# WIBL.net
KiCad netlist of a schematic drawn in EAGLE
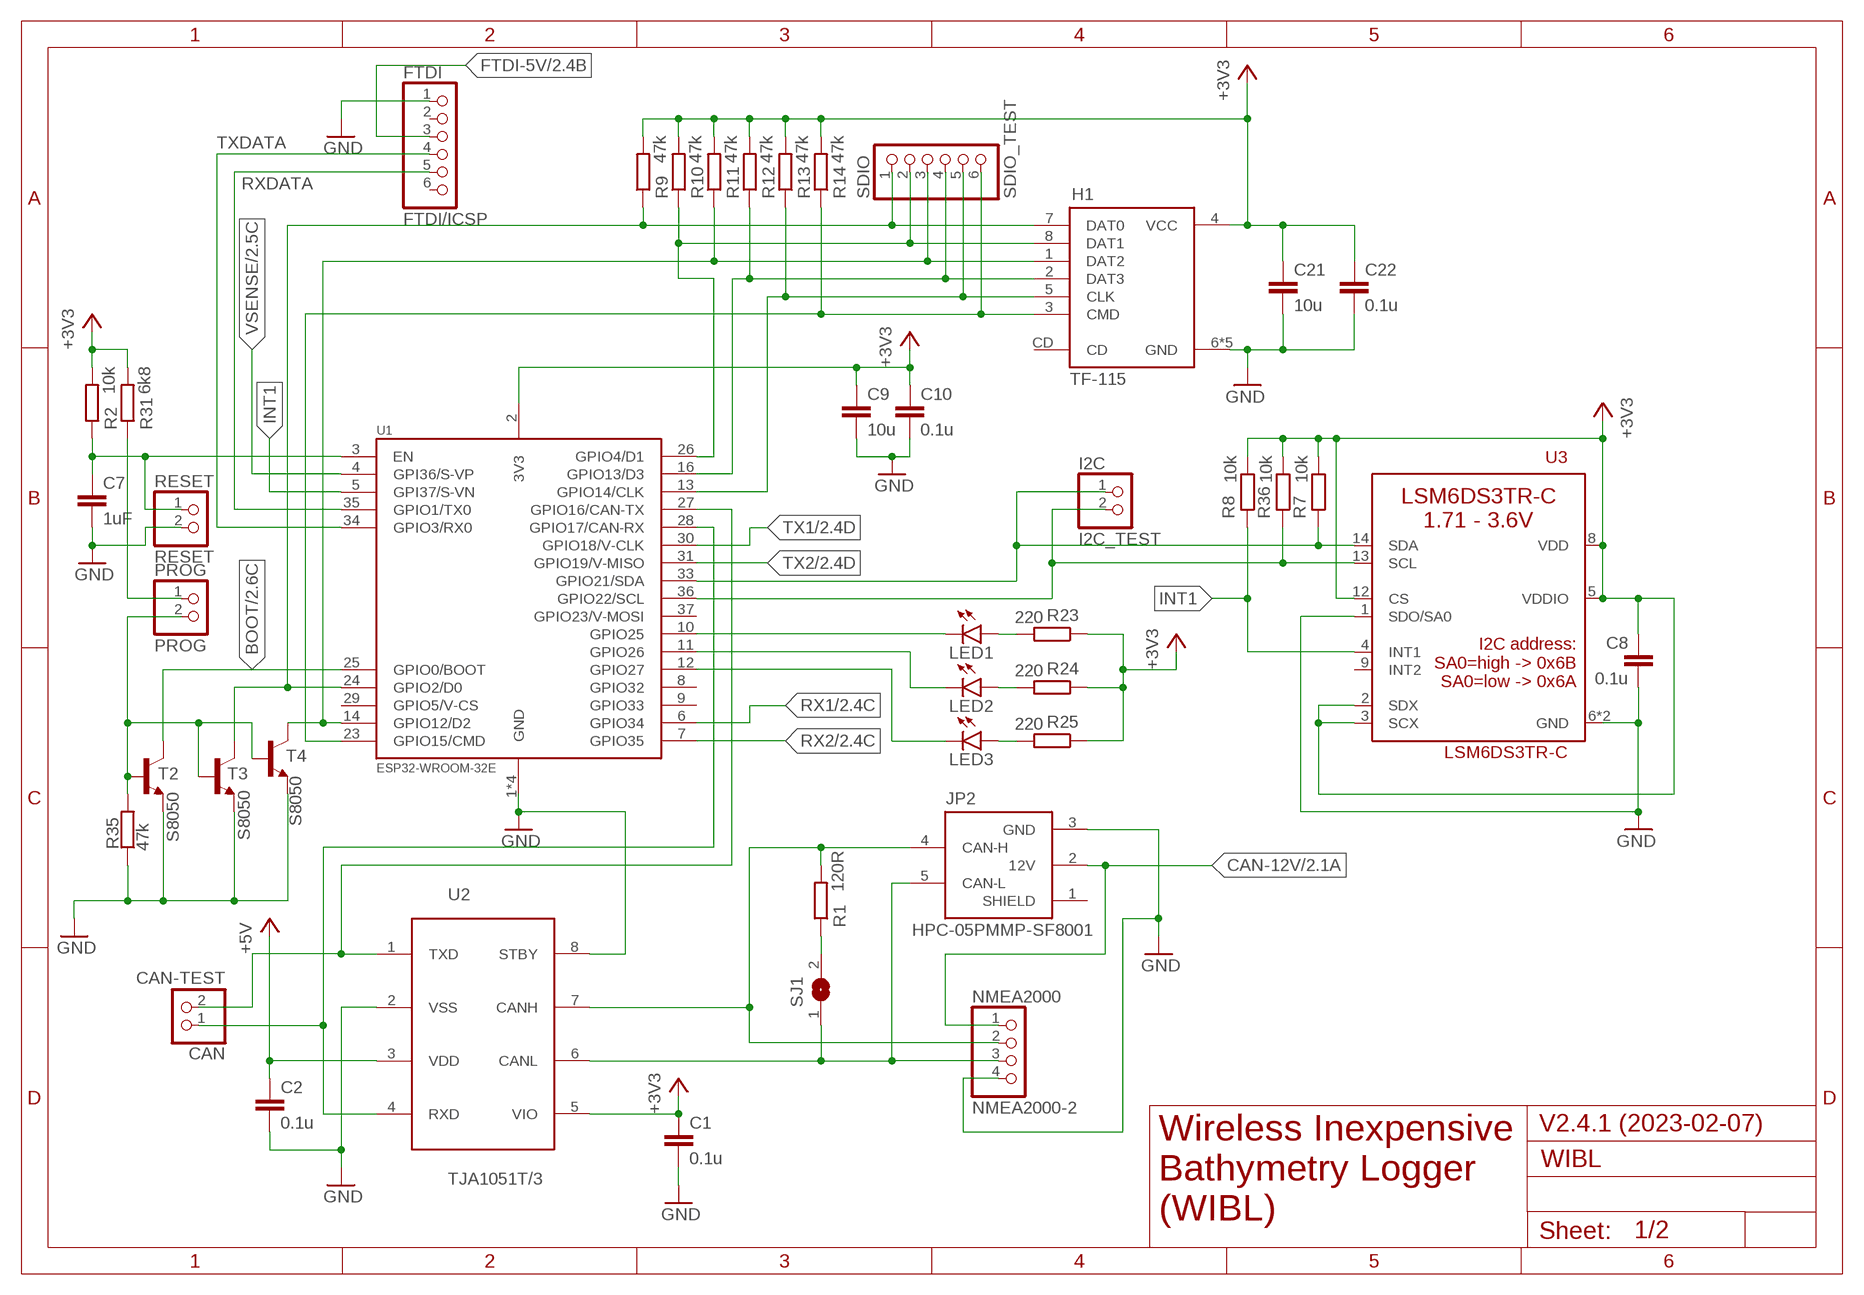
[diagram p0: schematic, sheet 1]
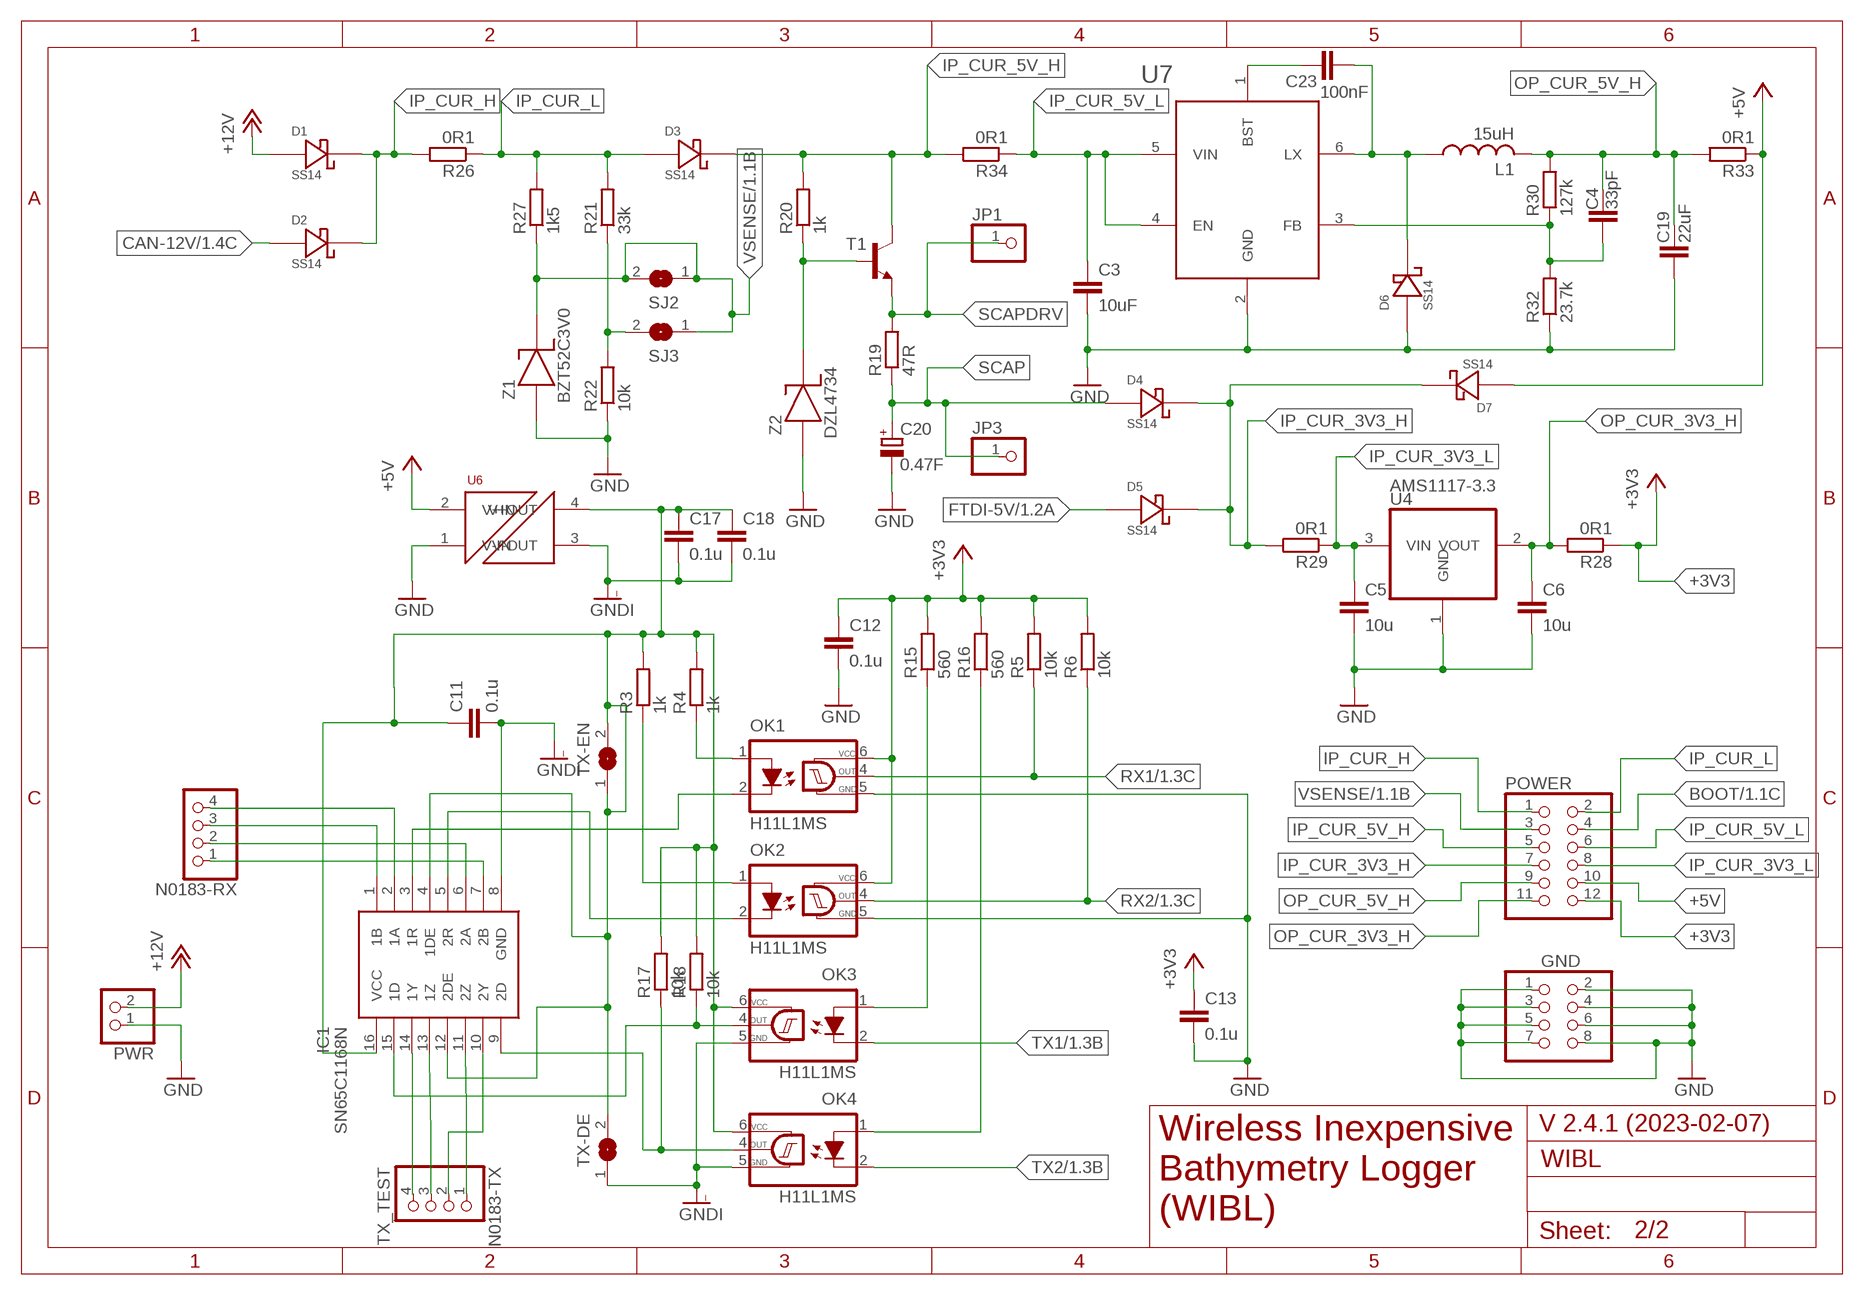
[diagram p1: schematic, sheet 2]

(export (version "E")
  (design (tool "Eeschema 10.0.6"))
  (components
    (comp (ref "C3")
      (value "10uF")
      (footprint "eagle-import:C1206")
      (libsource (lib "eagle-import") (part "C-EUC1206"))
    )
    (comp (ref "C4")
      (value "33pF")
      (footprint "eagle-import:C0603")
      (libsource (lib "eagle-import") (part "C-EUC0603"))
    )
    (comp (ref "C5")
      (value "10u")
      (footprint "eagle-import:C0805")
      (libsource (lib "eagle-import") (part "C-EUC0805"))
    )
    (comp (ref "C6")
      (value "10u")
      (footprint "eagle-import:C0805")
      (libsource (lib "eagle-import") (part "C-EUC0805"))
    )
    (comp (ref "C11")
      (value "0.1u")
      (footprint "eagle-import:C0805")
      (libsource (lib "eagle-import") (part "C-EUC0805"))
    )
    (comp (ref "C12")
      (value "0.1u")
      (footprint "eagle-import:C0805")
      (libsource (lib "eagle-import") (part "C-EUC0805"))
    )
    (comp (ref "C13")
      (value "0.1u")
      (footprint "eagle-import:C0805")
      (libsource (lib "eagle-import") (part "C-EUC0805"))
    )
    (comp (ref "C17")
      (value "0.1u")
      (footprint "eagle-import:C0805")
      (libsource (lib "eagle-import") (part "C-EUC0805"))
    )
    (comp (ref "C18")
      (value "0.1u")
      (footprint "eagle-import:C0805")
      (libsource (lib "eagle-import") (part "C-EUC0805"))
    )
    (comp (ref "C19")
      (value "22uF")
      (footprint "eagle-import:C0603")
      (libsource (lib "eagle-import") (part "C-EUC0603"))
    )
    (comp (ref "C20")
      (value "0.47F")
      (footprint "eagle-import:P128-50")
      (libsource (lib "eagle-import") (part "CPOL-EUP128-50"))
    )
    (comp (ref "C23")
      (value "100nF")
      (footprint "eagle-import:C0402")
      (libsource (lib "eagle-import") (part "C0402"))
    )
    (comp (ref "D1")
      (value "SS14")
      (footprint "eagle-import:DO-214AC")
      (libsource (lib "eagle-import") (part "SS14"))
    )
    (comp (ref "D2")
      (value "SS14")
      (footprint "eagle-import:DO-214AC")
      (libsource (lib "eagle-import") (part "SS14"))
    )
    (comp (ref "D3")
      (value "SS14")
      (footprint "eagle-import:DO-214AC")
      (libsource (lib "eagle-import") (part "SS14"))
    )
    (comp (ref "D4")
      (value "SS14")
      (footprint "eagle-import:DO-214AC")
      (libsource (lib "eagle-import") (part "SS14"))
    )
    (comp (ref "D5")
      (value "SS14")
      (footprint "eagle-import:DO-214AC")
      (libsource (lib "eagle-import") (part "SS14"))
    )
    (comp (ref "D6")
      (value "SS14")
      (footprint "eagle-import:DO-214AC")
      (libsource (lib "eagle-import") (part "SS14"))
    )
    (comp (ref "D7")
      (value "SS14")
      (footprint "eagle-import:DO-214AC")
      (libsource (lib "eagle-import") (part "SS14"))
    )
    (comp (ref "GND")
      (value "PINHD-2X4")
      (footprint "eagle-import:2X04")
      (libsource (lib "eagle-import") (part "PINHD-2X4"))
    )
    (comp (ref "IC1")
      (value "SN65C1168N")
      (footprint "eagle-import:DIP794W53P254L1930H508Q16N")
      (fields (field (name "MOUSER_PART_NUMBER") "595-SN65C1168N"))
      (libsource (lib "eagle-import") (part "SN65C1168N"))
    )
    (comp (ref "JP1")
      (value "PINHD-1X1")
      (footprint "eagle-import:1X01")
      (libsource (lib "eagle-import") (part "PINHD-1X1"))
    )
    (comp (ref "JP3")
      (value "PINHD-1X1")
      (footprint "eagle-import:1X01")
      (libsource (lib "eagle-import") (part "PINHD-1X1"))
    )
    (comp (ref "L1")
      (value "15uH")
      (footprint "eagle-import:MWSA0603S")
      (libsource (lib "eagle-import") (part "MWSA0603S"))
    )
    (comp (ref "N0183-RX")
      (value "PINHD-1X4")
      (footprint "eagle-import:1X04")
      (libsource (lib "eagle-import") (part "PINHD-1X4"))
    )
    (comp (ref "N0183-TX")
      (value "TX_TEST")
      (footprint "eagle-import:1X04")
      (libsource (lib "eagle-import") (part "PINHD-1X4"))
    )
    (comp (ref "OK1")
      (value "H11L1MS")
      (footprint "eagle-import:DIL6-SMD")
      (libsource (lib "eagle-import") (part "H11LMS1"))
    )
    (comp (ref "OK2")
      (value "H11L1MS")
      (footprint "eagle-import:DIL6-SMD")
      (libsource (lib "eagle-import") (part "H11LMS1"))
    )
    (comp (ref "OK3")
      (value "H11L1MS")
      (footprint "eagle-import:DIL6-SMD")
      (libsource (lib "eagle-import") (part "H11LMS1"))
    )
    (comp (ref "OK4")
      (value "H11L1MS")
      (footprint "eagle-import:DIL6-SMD")
      (libsource (lib "eagle-import") (part "H11LMS1"))
    )
    (comp (ref "POWER")
      (value "PINHD-2X6")
      (footprint "eagle-import:2X06")
      (libsource (lib "eagle-import") (part "PINHD-2X6"))
    )
    (comp (ref "PWR")
      (value "PINHD-1X2")
      (footprint "eagle-import:1X02")
      (libsource (lib "eagle-import") (part "PINHD-1X2"))
    )
    (comp (ref "R3")
      (value "1k")
      (footprint "eagle-import:R0805")
      (libsource (lib "eagle-import") (part "R-EU_R0805"))
    )
    (comp (ref "R4")
      (value "1k")
      (footprint "eagle-import:R0805")
      (libsource (lib "eagle-import") (part "R-EU_R0805"))
    )
    (comp (ref "R5")
      (value "10k")
      (footprint "eagle-import:R0805")
      (libsource (lib "eagle-import") (part "R-EU_R0805"))
    )
    (comp (ref "R6")
      (value "10k")
      (footprint "eagle-import:R0805")
      (libsource (lib "eagle-import") (part "R-EU_R0805"))
    )
    (comp (ref "R15")
      (value "560")
      (footprint "eagle-import:R0805")
      (libsource (lib "eagle-import") (part "R-EU_R0805"))
    )
    (comp (ref "R16")
      (value "560")
      (footprint "eagle-import:R0805")
      (libsource (lib "eagle-import") (part "R-EU_R0805"))
    )
    (comp (ref "R17")
      (value "10k")
      (footprint "eagle-import:R0805")
      (libsource (lib "eagle-import") (part "R-EU_R0805"))
    )
    (comp (ref "R18")
      (value "10k")
      (footprint "eagle-import:R0805")
      (libsource (lib "eagle-import") (part "R-EU_R0805"))
    )
    (comp (ref "R19")
      (value "47R")
      (footprint "eagle-import:R0805")
      (libsource (lib "eagle-import") (part "R-EU_R0805"))
    )
    (comp (ref "R20")
      (value "1k")
      (footprint "eagle-import:R0805")
      (libsource (lib "eagle-import") (part "R-EU_R0805"))
    )
    (comp (ref "R21")
      (value "33k")
      (footprint "eagle-import:R0805")
      (libsource (lib "eagle-import") (part "R-EU_R0805"))
    )
    (comp (ref "R22")
      (value "10k")
      (footprint "eagle-import:R0805")
      (libsource (lib "eagle-import") (part "R-EU_R0805"))
    )
    (comp (ref "R26")
      (value "0R1")
      (footprint "eagle-import:R0603")
      (libsource (lib "eagle-import") (part "R-EU_R0603"))
    )
    (comp (ref "R27")
      (value "1k5")
      (footprint "eagle-import:R0805")
      (libsource (lib "eagle-import") (part "R-EU_R0805"))
    )
    (comp (ref "R28")
      (value "0R1")
      (footprint "eagle-import:R0603")
      (libsource (lib "eagle-import") (part "R-EU_R0603"))
    )
    (comp (ref "R29")
      (value "0R1")
      (footprint "eagle-import:R0603")
      (libsource (lib "eagle-import") (part "R-EU_R0603"))
    )
    (comp (ref "R30")
      (value "127k")
      (footprint "eagle-import:R0603")
      (libsource (lib "eagle-import") (part "R-EU_R0603"))
    )
    (comp (ref "R32")
      (value "23.7k")
      (footprint "eagle-import:R0603")
      (libsource (lib "eagle-import") (part "R-EU_R0603"))
    )
    (comp (ref "R33")
      (value "0R1")
      (footprint "eagle-import:R0603")
      (libsource (lib "eagle-import") (part "R-EU_R0603"))
    )
    (comp (ref "R34")
      (value "0R1")
      (footprint "eagle-import:R0603")
      (libsource (lib "eagle-import") (part "R-EU_R0603"))
    )
    (comp (ref "SJ2") (value "SJ") (footprint "eagle-import:SJ") (libsource (lib "eagle-import") (part "SJ")))
    (comp (ref "SJ3") (value "SJ") (footprint "eagle-import:SJ") (libsource (lib "eagle-import") (part "SJ")))
    (comp (ref "T1")
      (value "BC817-16-NPN-SOT23-BEC")
      (footprint "eagle-import:SOT23-BEC")
      (libsource (lib "eagle-import") (part "-NPN-SOT23-BECBC817-16"))
    )
    (comp (ref "TX-DE")
      (value "SJ")
      (footprint "eagle-import:SJ")
      (libsource (lib "eagle-import") (part "SJ"))
    )
    (comp (ref "TX-EN")
      (value "SJ")
      (footprint "eagle-import:SJ")
      (libsource (lib "eagle-import") (part "SJ"))
    )
    (comp (ref "U4")
      (value "AMS1117-3.3")
      (footprint "eagle-import:SOT223")
      (fields (field (name "MPN") "REG1117"))
      (libsource (lib "eagle-import") (part "REG1117"))
    )
    (comp (ref "U6")
      (value "RFM-0505S")
      (footprint "eagle-import:RFM-0505S")
      (libsource (lib "eagle-import") (part "RFM-0505S"))
    )
    (comp (ref "U7")
      (value "BL9352A")
      (footprint "eagle-import:SOT-23-6L")
      (libsource (lib "eagle-import") (part "BL9352A"))
    )
    (comp (ref "Z1")
      (value "BZT52C3V0")
      (footprint "eagle-import:SOD123")
      (libsource (lib "eagle-import") (part "BZT52C3V0"))
    )
    (comp (ref "Z2")
      (value "DZL4734")
      (footprint "eagle-import:SOD-123FL")
      (libsource (lib "eagle-import") (part "DZL4734"))
    )
    (comp (ref "C1")
      (value "0.1u")
      (footprint "eagle-import:C0805")
      (libsource (lib "eagle-import") (part "C-EUC0805"))
    )
    (comp (ref "C2")
      (value "0.1u")
      (footprint "eagle-import:C0805")
      (libsource (lib "eagle-import") (part "C-EUC0805"))
    )
    (comp (ref "C7")
      (value "1uF")
      (footprint "eagle-import:C0805")
      (libsource (lib "eagle-import") (part "C-EUC0805"))
    )
    (comp (ref "C8")
      (value "0.1u")
      (footprint "eagle-import:C0805")
      (libsource (lib "eagle-import") (part "C-EUC0805"))
    )
    (comp (ref "C9")
      (value "10u")
      (footprint "eagle-import:C0805")
      (libsource (lib "eagle-import") (part "C-EUC0805"))
    )
    (comp (ref "C10")
      (value "0.1u")
      (footprint "eagle-import:C0805")
      (libsource (lib "eagle-import") (part "C-EUC0805"))
    )
    (comp (ref "C21")
      (value "10u")
      (footprint "eagle-import:C0805")
      (libsource (lib "eagle-import") (part "C-EUC0805"))
    )
    (comp (ref "C22")
      (value "0.1u")
      (footprint "eagle-import:C0805")
      (libsource (lib "eagle-import") (part "C-EUC0805"))
    )
    (comp (ref "CAN")
      (value "CAN-TEST")
      (footprint "eagle-import:1X02")
      (libsource (lib "eagle-import") (part "PINHD-1X2"))
    )
    (comp (ref "FTDI")
      (value "FTDI/ICSP")
      (footprint "eagle-import:1X06")
      (libsource (lib "eagle-import") (part "PINHD-1X6"))
    )
    (comp (ref "H1")
      (value "TF-115")
      (footprint "eagle-import:XUNPU-MICROSD-SOCKET")
      (libsource (lib "eagle-import") (part "XUNPU-MICROSD-SOCKET"))
    )
    (comp (ref "I2C")
      (value "I2C_TEST")
      (footprint "eagle-import:1X02")
      (libsource (lib "eagle-import") (part "PINHD-1X2"))
    )
    (comp (ref "JP2")
      (value "HPC-05PMMP-SF8001")
      (footprint "eagle-import:NMEA2000")
      (libsource (lib "eagle-import") (part "NMEA2000"))
    )
    (comp (ref "LED1")
      (value "LEDCHIP-LED0603")
      (footprint "eagle-import:CHIP-LED0603")
      (libsource (lib "eagle-import") (part "LEDCHIP-LED0603"))
    )
    (comp (ref "LED2")
      (value "LEDCHIP-LED0603")
      (footprint "eagle-import:CHIP-LED0603")
      (libsource (lib "eagle-import") (part "LEDCHIP-LED0603"))
    )
    (comp (ref "LED3")
      (value "LEDCHIP-LED0603")
      (footprint "eagle-import:CHIP-LED0603")
      (libsource (lib "eagle-import") (part "LEDCHIP-LED0603"))
    )
    (comp (ref "NMEA2000")
      (value "NMEA2000-2")
      (footprint "eagle-import:1X04")
      (libsource (lib "eagle-import") (part "PINHD-1X4"))
    )
    (comp (ref "PROG")
      (value "PROG")
      (footprint "eagle-import:1X02")
      (libsource (lib "eagle-import") (part "PINHD-1X2"))
    )
    (comp (ref "R1")
      (value "120R")
      (footprint "eagle-import:R0805")
      (libsource (lib "eagle-import") (part "R-EU_R0805"))
    )
    (comp (ref "R2")
      (value "10k")
      (footprint "eagle-import:R0805")
      (libsource (lib "eagle-import") (part "R-EU_R0805"))
    )
    (comp (ref "R7")
      (value "10k")
      (footprint "eagle-import:R0805")
      (libsource (lib "eagle-import") (part "R-EU_R0805"))
    )
    (comp (ref "R8")
      (value "10k")
      (footprint "eagle-import:R0805")
      (libsource (lib "eagle-import") (part "R-EU_R0805"))
    )
    (comp (ref "R9")
      (value "47k")
      (footprint "eagle-import:R0805")
      (libsource (lib "eagle-import") (part "R-EU_R0805"))
    )
    (comp (ref "R10")
      (value "47k")
      (footprint "eagle-import:R0805")
      (libsource (lib "eagle-import") (part "R-EU_R0805"))
    )
    (comp (ref "R11")
      (value "47k")
      (footprint "eagle-import:R0805")
      (libsource (lib "eagle-import") (part "R-EU_R0805"))
    )
    (comp (ref "R12")
      (value "47k")
      (footprint "eagle-import:R0805")
      (libsource (lib "eagle-import") (part "R-EU_R0805"))
    )
    (comp (ref "R13")
      (value "47k")
      (footprint "eagle-import:R0805")
      (libsource (lib "eagle-import") (part "R-EU_R0805"))
    )
    (comp (ref "R14")
      (value "47k")
      (footprint "eagle-import:R0805")
      (libsource (lib "eagle-import") (part "R-EU_R0805"))
    )
    (comp (ref "R23")
      (value "220")
      (footprint "eagle-import:R0805")
      (libsource (lib "eagle-import") (part "R-EU_R0805"))
    )
    (comp (ref "R24")
      (value "220")
      (footprint "eagle-import:R0805")
      (libsource (lib "eagle-import") (part "R-EU_R0805"))
    )
    (comp (ref "R25")
      (value "220")
      (footprint "eagle-import:R0805")
      (libsource (lib "eagle-import") (part "R-EU_R0805"))
    )
    (comp (ref "R31")
      (value "6k8")
      (footprint "eagle-import:R0805")
      (libsource (lib "eagle-import") (part "R-EU_R0805"))
    )
    (comp (ref "R35")
      (value "47k")
      (footprint "eagle-import:R0805")
      (libsource (lib "eagle-import") (part "R-EU_R0805"))
    )
    (comp (ref "R36")
      (value "10k")
      (footprint "eagle-import:R0805")
      (libsource (lib "eagle-import") (part "R-EU_R0805"))
    )
    (comp (ref "RESET")
      (value "RESET")
      (footprint "eagle-import:1X02")
      (libsource (lib "eagle-import") (part "PINHD-1X2"))
    )
    (comp (ref "SDIO")
      (value "SDIO_TEST")
      (footprint "eagle-import:1X06")
      (libsource (lib "eagle-import") (part "PINHD-1X6"))
    )
    (comp (ref "SJ1") (value "SJ") (footprint "eagle-import:SJ") (libsource (lib "eagle-import") (part "SJ")))
    (comp (ref "T2")
      (value "S8050")
      (footprint "eagle-import:SOT23")
      (libsource (lib "eagle-import") (part "BC846"))
    )
    (comp (ref "T3")
      (value "S8050")
      (footprint "eagle-import:SOT23")
      (libsource (lib "eagle-import") (part "BC846"))
    )
    (comp (ref "T4")
      (value "S8050")
      (footprint "eagle-import:SOT23")
      (libsource (lib "eagle-import") (part "BC846"))
    )
    (comp (ref "U1")
      (value "ESP32-WROOM-32E")
      (footprint "eagle-import:ESPS32-WROOM-32E")
      (libsource (lib "eagle-import") (part "ESP32-WROOM-32E"))
    )
    (comp (ref "U2")
      (value "TJA1051T/3")
      (footprint "eagle-import:SOIC8")
      (libsource (lib "eagle-import") (part "MCP2562T-E/SN"))
    )
    (comp (ref "U3")
      (value "LSM6DS3TR-C")
      (footprint "eagle-import:LGA-14-2.5X3MM")
      (fields (field (name "MF") "STMicroelectronics"))
      (libsource (lib "eagle-import") (part "LSM6DS3TR-C"))
    )
  )
  (nets
    (net (code "1") (name "+3V3") (class "Default")
      (node (ref "C1") (pin "1") (pinfunction "1_1") (pintype "passive"))
      (node (ref "C10") (pin "1") (pinfunction "1_1") (pintype "passive"))
      (node (ref "C12") (pin "1") (pinfunction "1_1") (pintype "passive"))
      (node (ref "C13") (pin "1") (pinfunction "1_1") (pintype "passive"))
      (node (ref "C21") (pin "1") (pinfunction "1_1") (pintype "passive"))
      (node (ref "C22") (pin "1") (pinfunction "1_1") (pintype "passive"))
      (node (ref "C8") (pin "1") (pinfunction "1_1") (pintype "passive"))
      (node (ref "C9") (pin "1") (pinfunction "1_1") (pintype "passive"))
      (node (ref "H1") (pin "4") (pinfunction "VCC_4") (pintype "bidirectional"))
      (node (ref "OK1") (pin "6") (pinfunction "VCC_6") (pintype "power_in"))
      (node (ref "OK2") (pin "6") (pinfunction "VCC_6") (pintype "power_in"))
      (node (ref "POWER") (pin "12") (pinfunction "12_12") (pintype "passive"))
      (node (ref "R10") (pin "2") (pinfunction "2_2") (pintype "passive"))
      (node (ref "R11") (pin "2") (pinfunction "2_2") (pintype "passive"))
      (node (ref "R12") (pin "2") (pinfunction "2_2") (pintype "passive"))
      (node (ref "R13") (pin "2") (pinfunction "2_2") (pintype "passive"))
      (node (ref "R14") (pin "2") (pinfunction "2_2") (pintype "passive"))
      (node (ref "R15") (pin "2") (pinfunction "2_2") (pintype "passive"))
      (node (ref "R16") (pin "2") (pinfunction "2_2") (pintype "passive"))
      (node (ref "R2") (pin "2") (pinfunction "2_2") (pintype "passive"))
      (node (ref "R23") (pin "1") (pinfunction "1_1") (pintype "passive"))
      (node (ref "R24") (pin "1") (pinfunction "1_1") (pintype "passive"))
      (node (ref "R25") (pin "1") (pinfunction "1_1") (pintype "passive"))
      (node (ref "R28") (pin "1") (pinfunction "1_1") (pintype "passive"))
      (node (ref "R31") (pin "2") (pinfunction "2_2") (pintype "passive"))
      (node (ref "R36") (pin "2") (pinfunction "2_2") (pintype "passive"))
      (node (ref "R5") (pin "2") (pinfunction "2_2") (pintype "passive"))
      (node (ref "R6") (pin "2") (pinfunction "2_2") (pintype "passive"))
      (node (ref "R7") (pin "2") (pinfunction "2_2") (pintype "passive"))
      (node (ref "R8") (pin "2") (pinfunction "2_2") (pintype "passive"))
      (node (ref "R9") (pin "2") (pinfunction "2_2") (pintype "passive"))
      (node (ref "U1") (pin "2") (pinfunction "3V3_2") (pintype "bidirectional"))
      (node (ref "U2") (pin "5") (pinfunction "VIO_5") (pintype "bidirectional"))
      (node (ref "U3") (pin "12") (pinfunction "CS_12") (pintype "bidirectional"))
      (node (ref "U3") (pin "2") (pinfunction "SDX_2") (pintype "bidirectional"))
      (node (ref "U3") (pin "3") (pinfunction "SCX_3") (pintype "bidirectional"))
      (node (ref "U3") (pin "5") (pinfunction "VDDIO_5") (pintype "bidirectional"))
      (node (ref "U3") (pin "8") (pinfunction "VDD_8") (pintype "bidirectional"))
    )
    (net (code "2") (name "+5V") (class "Default")
      (node (ref "C2") (pin "1") (pinfunction "1_1") (pintype "passive"))
      (node (ref "D7") (pin "A") (pinfunction "A_A") (pintype "bidirectional"))
      (node (ref "POWER") (pin "10") (pinfunction "10_10") (pintype "passive"))
      (node (ref "R33") (pin "1") (pinfunction "1_1") (pintype "passive"))
      (node (ref "U2") (pin "3") (pinfunction "VDD_3") (pintype "bidirectional"))
      (node (ref "U6") (pin "2") (pinfunction "V+IN_2") (pintype "bidirectional"))
    )
    (net (code "3") (name "+12V") (class "Default")
      (node (ref "D1") (pin "A") (pinfunction "A_A") (pintype "bidirectional"))
      (node (ref "PWR") (pin "2") (pinfunction "2_2") (pintype "passive"))
    )
    (net (code "4") (name "BOOT") (class "Default")
      (node (ref "POWER") (pin "4") (pinfunction "4_4") (pintype "passive"))
      (node (ref "T2") (pin "3") (pinfunction "C_3") (pintype "passive"))
      (node (ref "U1") (pin "25") (pinfunction "GPIO0/BOOT_25") (pintype "bidirectional"))
    )
    (net (code "5") (name "CAN-12V") (class "Default")
      (node (ref "D2") (pin "A") (pinfunction "A_A") (pintype "bidirectional"))
      (node (ref "JP2") (pin "2") (pinfunction "12V_2") (pintype "bidirectional"))
      (node (ref "NMEA2000") (pin "1") (pinfunction "1_1") (pintype "passive"))
    )
    (net (code "6") (name "FTDI-5V") (class "Default")
      (node (ref "D5") (pin "A") (pinfunction "A_A") (pintype "bidirectional"))
      (node (ref "FTDI") (pin "3") (pinfunction "3_3") (pintype "passive"))
    )
    (net (code "7") (name "GND") (class "Default")
      (node (ref "C1") (pin "2") (pinfunction "2_2") (pintype "passive"))
      (node (ref "C10") (pin "2") (pinfunction "2_2") (pintype "passive"))
      (node (ref "C12") (pin "2") (pinfunction "2_2") (pintype "passive"))
      (node (ref "C13") (pin "2") (pinfunction "2_2") (pintype "passive"))
      (node (ref "C19") (pin "1") (pinfunction "1_1") (pintype "passive"))
      (node (ref "C2") (pin "2") (pinfunction "2_2") (pintype "passive"))
      (node (ref "C20") (pin "-") (pinfunction "-_-") (pintype "passive"))
      (node (ref "C21") (pin "2") (pinfunction "2_2") (pintype "passive"))
      (node (ref "C22") (pin "2") (pinfunction "2_2") (pintype "passive"))
      (node (ref "C3") (pin "2") (pinfunction "2_2") (pintype "passive"))
      (node (ref "C5") (pin "2") (pinfunction "2_2") (pintype "passive"))
      (node (ref "C6") (pin "2") (pinfunction "2_2") (pintype "passive"))
      (node (ref "C7") (pin "2") (pinfunction "2_2") (pintype "passive"))
      (node (ref "C8") (pin "2") (pinfunction "2_2") (pintype "passive"))
      (node (ref "C9") (pin "2") (pinfunction "2_2") (pintype "passive"))
      (node (ref "D6") (pin "A") (pinfunction "A_A") (pintype "bidirectional"))
      (node (ref "FTDI") (pin "1") (pinfunction "1_1") (pintype "passive"))
      (node (ref "GND") (pin "1") (pinfunction "1_1") (pintype "passive"))
      (node (ref "GND") (pin "2") (pinfunction "2_2") (pintype "passive"))
      (node (ref "GND") (pin "3") (pinfunction "3_3") (pintype "passive"))
      (node (ref "GND") (pin "4") (pinfunction "4_4") (pintype "passive"))
      (node (ref "GND") (pin "5") (pinfunction "5_5") (pintype "passive"))
      (node (ref "GND") (pin "6") (pinfunction "6_6") (pintype "passive"))
      (node (ref "GND") (pin "7") (pinfunction "7_7") (pintype "passive"))
      (node (ref "GND") (pin "8") (pinfunction "8_8") (pintype "passive"))
      (node (ref "H1") (pin "6") (pinfunction "GND_6") (pintype "bidirectional"))
      (node (ref "H1") (pin "GND1") (pinfunction "GND_GND1") (pintype "bidirectional"))
      (node (ref "H1") (pin "GND2") (pinfunction "GND_GND2") (pintype "bidirectional"))
      (node (ref "H1") (pin "GND3") (pinfunction "GND_GND3") (pintype "bidirectional"))
      (node (ref "H1") (pin "GND4") (pinfunction "GND_GND4") (pintype "bidirectional"))
      (node (ref "JP2") (pin "3") (pinfunction "GND_3") (pintype "bidirectional"))
      (node (ref "NMEA2000") (pin "4") (pinfunction "4_4") (pintype "passive"))
      (node (ref "OK1") (pin "5") (pinfunction "GND_5") (pintype "power_in"))
      (node (ref "OK2") (pin "5") (pinfunction "GND_5") (pintype "power_in"))
      (node (ref "PWR") (pin "1") (pinfunction "1_1") (pintype "passive"))
      (node (ref "R22") (pin "1") (pinfunction "1_1") (pintype "passive"))
      (node (ref "R32") (pin "1") (pinfunction "1_1") (pintype "passive"))
      (node (ref "R35") (pin "1") (pinfunction "1_1") (pintype "passive"))
      (node (ref "RESET") (pin "2") (pinfunction "2_2") (pintype "passive"))
      (node (ref "T2") (pin "2") (pinfunction "E_2") (pintype "passive"))
      (node (ref "T3") (pin "2") (pinfunction "E_2") (pintype "passive"))
      (node (ref "T4") (pin "2") (pinfunction "E_2") (pintype "passive"))
      (node (ref "U1") (pin "1") (pinfunction "GND_1") (pintype "bidirectional"))
      (node (ref "U1") (pin "15") (pinfunction "GND_15") (pintype "bidirectional"))
      (node (ref "U1") (pin "38") (pinfunction "GND_38") (pintype "bidirectional"))
      (node (ref "U1") (pin "THERM") (pinfunction "GND_THERM") (pintype "bidirectional"))
      (node (ref "U2") (pin "2") (pinfunction "VSS_2") (pintype "bidirectional"))
      (node (ref "U2") (pin "8") (pinfunction "STBY_8") (pintype "bidirectional"))
      (node (ref "U3") (pin "1") (pinfunction "SDO/SA0_1") (pintype "bidirectional"))
      (node (ref "U3") (pin "6") (pinfunction "GND_6") (pintype "bidirectional"))
      (node (ref "U3") (pin "7") (pinfunction "GND_7") (pintype "bidirectional"))
      (node (ref "U4") (pin "1") (pinfunction "GND_1") (pintype "power_in"))
      (node (ref "U6") (pin "1") (pinfunction "V-IN_1") (pintype "bidirectional"))
      (node (ref "U7") (pin "2") (pinfunction "GND_2") (pintype "bidirectional"))
      (node (ref "Z1") (pin "1") (pinfunction "A_1") (pintype "bidirectional"))
      (node (ref "Z2") (pin "A") (pinfunction "A_A") (pintype "bidirectional"))
    )
    (net (code "8") (name "GNDI") (class "Default")
      (node (ref "C11") (pin "2") (pinfunction "2_2") (pintype "passive"))
      (node (ref "C17") (pin "2") (pinfunction "2_2") (pintype "passive"))
      (node (ref "C18") (pin "2") (pinfunction "2_2") (pintype "passive"))
      (node (ref "IC1") (pin "8") (pinfunction "GND_8") (pintype "power_in"))
      (node (ref "OK3") (pin "5") (pinfunction "GND_5") (pintype "power_in"))
      (node (ref "OK4") (pin "5") (pinfunction "GND_5") (pintype "power_in"))
      (node (ref "TX-DE") (pin "1") (pinfunction "1_1") (pintype "passive"))
      (node (ref "U6") (pin "3") (pinfunction "V-OUT_3") (pintype "bidirectional"))
    )
    (net (code "9") (name "INT1") (class "Default")
      (node (ref "R8") (pin "1") (pinfunction "1_1") (pintype "passive"))
      (node (ref "U1") (pin "5") (pinfunction "GPI37/S-VN_5") (pintype "bidirectional"))
      (node (ref "U3") (pin "4") (pinfunction "INT1_4") (pintype "bidirectional"))
    )
    (net (code "10") (name "IP_CUR_3V3_H") (class "Default")
      (node (ref "D4") (pin "K") (pinfunction "K_K") (pintype "bidirectional"))
      (node (ref "D5") (pin "K") (pinfunction "K_K") (pintype "bidirectional"))
      (node (ref "D7") (pin "K") (pinfunction "K_K") (pintype "bidirectional"))
      (node (ref "POWER") (pin "7") (pinfunction "7_7") (pintype "passive"))
      (node (ref "R29") (pin "2") (pinfunction "2_2") (pintype "passive"))
    )
    (net (code "11") (name "IP_CUR_3V3_L") (class "Default")
      (node (ref "C5") (pin "1") (pinfunction "1_1") (pintype "passive"))
      (node (ref "POWER") (pin "8") (pinfunction "8_8") (pintype "passive"))
      (node (ref "R29") (pin "1") (pinfunction "1_1") (pintype "passive"))
      (node (ref "U4") (pin "3") (pinfunction "VIN_3") (pintype "input"))
    )
    (net (code "12") (name "IP_CUR_5V_H") (class "Default")
      (node (ref "D3") (pin "K") (pinfunction "K_K") (pintype "bidirectional"))
      (node (ref "POWER") (pin "5") (pinfunction "5_5") (pintype "passive"))
      (node (ref "R20") (pin "2") (pinfunction "2_2") (pintype "passive"))
      (node (ref "R34") (pin "2") (pinfunction "2_2") (pintype "passive"))
      (node (ref "T1") (pin "C") (pinfunction "C_C") (pintype "passive"))
    )
    (net (code "13") (name "IP_CUR_5V_L") (class "Default")
      (node (ref "C3") (pin "1") (pinfunction "1_1") (pintype "passive"))
      (node (ref "POWER") (pin "6") (pinfunction "6_6") (pintype "passive"))
      (node (ref "R34") (pin "1") (pinfunction "1_1") (pintype "passive"))
      (node (ref "U7") (pin "4") (pinfunction "EN_4") (pintype "bidirectional"))
      (node (ref "U7") (pin "5") (pinfunction "VIN_5") (pintype "bidirectional"))
    )
    (net (code "14") (name "IP_CUR_H") (class "Default")
      (node (ref "D1") (pin "K") (pinfunction "K_K") (pintype "bidirectional"))
      (node (ref "D2") (pin "K") (pinfunction "K_K") (pintype "bidirectional"))
      (node (ref "POWER") (pin "1") (pinfunction "1_1") (pintype "passive"))
      (node (ref "R26") (pin "2") (pinfunction "2_2") (pintype "passive"))
    )
    (net (code "15") (name "IP_CUR_L") (class "Default")
      (node (ref "D3") (pin "A") (pinfunction "A_A") (pintype "bidirectional"))
      (node (ref "POWER") (pin "2") (pinfunction "2_2") (pintype "passive"))
      (node (ref "R21") (pin "2") (pinfunction "2_2") (pintype "passive"))
      (node (ref "R26") (pin "1") (pinfunction "1_1") (pintype "passive"))
      (node (ref "R27") (pin "2") (pinfunction "2_2") (pintype "passive"))
    )
    (net (code "16") (name "Net-(C23-1)") (class "Default")
      (node (ref "C23") (pin "P$1") (pinfunction "1_P$1") (pintype "passive"))
      (node (ref "U7") (pin "1") (pinfunction "BST_1") (pintype "bidirectional"))
    )
    (net (code "17") (name "Net-(C23-2)") (class "Default")
      (node (ref "C23") (pin "P$2") (pinfunction "2_P$2") (pintype "passive"))
      (node (ref "D6") (pin "K") (pinfunction "K_K") (pintype "bidirectional"))
      (node (ref "L1") (pin "P$1") (pinfunction "1_P$1") (pintype "passive"))
      (node (ref "U7") (pin "6") (pinfunction "LX_6") (pintype "bidirectional"))
    )
    (net (code "18") (name "Net-(H1-CLK)") (class "Default")
      (node (ref "H1") (pin "5") (pinfunction "CLK_5") (pintype "bidirectional"))
      (node (ref "R13") (pin "1") (pinfunction "1_1") (pintype "passive"))
      (node (ref "SDIO") (pin "5") (pinfunction "5_5") (pintype "passive"))
      (node (ref "U1") (pin "13") (pinfunction "GPIO14/CLK_13") (pintype "bidirectional"))
    )
    (net (code "19") (name "Net-(H1-CMD)") (class "Default")
      (node (ref "H1") (pin "3") (pinfunction "CMD_3") (pintype "bidirectional"))
      (node (ref "R14") (pin "1") (pinfunction "1_1") (pintype "passive"))
      (node (ref "SDIO") (pin "6") (pinfunction "6_6") (pintype "passive"))
      (node (ref "U1") (pin "23") (pinfunction "GPIO15/CMD_23") (pintype "bidirectional"))
    )
    (net (code "20") (name "Net-(H1-DAT0)") (class "Default")
      (node (ref "H1") (pin "7") (pinfunction "DAT0_7") (pintype "bidirectional"))
      (node (ref "R9") (pin "1") (pinfunction "1_1") (pintype "passive"))
      (node (ref "SDIO") (pin "1") (pinfunction "1_1") (pintype "passive"))
      (node (ref "T3") (pin "3") (pinfunction "C_3") (pintype "passive"))
      (node (ref "U1") (pin "24") (pinfunction "GPIO2/D0_24") (pintype "bidirectional"))
    )
    (net (code "21") (name "Net-(H1-DAT1)") (class "Default")
      (node (ref "H1") (pin "8") (pinfunction "DAT1_8") (pintype "bidirectional"))
      (node (ref "R10") (pin "1") (pinfunction "1_1") (pintype "passive"))
      (node (ref "SDIO") (pin "2") (pinfunction "2_2") (pintype "passive"))
      (node (ref "U1") (pin "26") (pinfunction "GPIO4/D1_26") (pintype "bidirectional"))
    )
    (net (code "22") (name "Net-(H1-DAT2)") (class "Default")
      (node (ref "H1") (pin "1") (pinfunction "DAT2_1") (pintype "bidirectional"))
      (node (ref "R11") (pin "1") (pinfunction "1_1") (pintype "passive"))
      (node (ref "SDIO") (pin "3") (pinfunction "3_3") (pintype "passive"))
      (node (ref "T4") (pin "3") (pinfunction "C_3") (pintype "passive"))
      (node (ref "U1") (pin "14") (pinfunction "GPIO12/D2_14") (pintype "bidirectional"))
    )
    (net (code "23") (name "Net-(H1-DAT3)") (class "Default")
      (node (ref "H1") (pin "2") (pinfunction "DAT3_2") (pintype "bidirectional"))
      (node (ref "R12") (pin "1") (pinfunction "1_1") (pintype "passive"))
      (node (ref "SDIO") (pin "4") (pinfunction "4_4") (pintype "passive"))
      (node (ref "U1") (pin "16") (pinfunction "GPIO13/D3_16") (pintype "bidirectional"))
    )
    (net (code "24") (name "Net-(IC1-1A)") (class "Default")
      (node (ref "IC1") (pin "2") (pinfunction "1A_2") (pintype "input"))
      (node (ref "N0183-RX") (pin "4") (pinfunction "4_4") (pintype "passive"))
    )
    (net (code "25") (name "Net-(IC1-1B)") (class "Default")
      (node (ref "IC1") (pin "1") (pinfunction "1B_1") (pintype "input"))
      (node (ref "N0183-RX") (pin "3") (pinfunction "3_3") (pintype "passive"))
    )
    (net (code "26") (name "Net-(IC1-1D)") (class "Default")
      (node (ref "IC1") (pin "15") (pinfunction "1D_15") (pintype "input"))
      (node (ref "OK3") (pin "4") (pinfunction "OUT_4") (pintype "output"))
      (node (ref "R18") (pin "1") (pinfunction "1_1") (pintype "passive"))
    )
    (net (code "27") (name "Net-(IC1-1DE)") (class "Default")
      (node (ref "C11") (pin "1") (pinfunction "1_1") (pintype "passive"))
      (node (ref "C17") (pin "1") (pinfunction "1_1") (pintype "passive"))
      (node (ref "C18") (pin "1") (pinfunction "1_1") (pintype "passive"))
      (node (ref "IC1") (pin "12") (pinfunction "2DE_12") (pintype "input"))
      (node (ref "IC1") (pin "16") (pinfunction "VCC_16") (pintype "power_in"))
      (node (ref "IC1") (pin "4") (pinfunction "1DE_4") (pintype "input"))
      (node (ref "OK3") (pin "6") (pinfunction "VCC_6") (pintype "power_in"))
      (node (ref "OK4") (pin "6") (pinfunction "VCC_6") (pintype "power_in"))
      (node (ref "R17") (pin "2") (pinfunction "2_2") (pintype "passive"))
      (node (ref "R18") (pin "2") (pinfunction "2_2") (pintype "passive"))
      (node (ref "R3") (pin "2") (pinfunction "2_2") (pintype "passive"))
      (node (ref "R4") (pin "2") (pinfunction "2_2") (pintype "passive"))
      (node (ref "TX-DE") (pin "2") (pinfunction "2_2") (pintype "passive"))
      (node (ref "TX-EN") (pin "1") (pinfunction "1_1") (pintype "passive"))
      (node (ref "TX-EN") (pin "2") (pinfunction "2_2") (pintype "passive"))
      (node (ref "U6") (pin "4") (pinfunction "V+OUT_4") (pintype "bidirectional"))
    )
    (net (code "28") (name "Net-(IC1-1R)") (class "Default")
      (node (ref "IC1") (pin "3") (pinfunction "1R_3") (pintype "output"))
      (node (ref "OK1") (pin "2") (pinfunction "C_2") (pintype "passive"))
    )
    (net (code "29") (name "Net-(IC1-1Y)") (class "Default")
      (node (ref "IC1") (pin "14") (pinfunction "1Y_14") (pintype "output"))
      (node (ref "N0183-TX") (pin "4") (pinfunction "4_4") (pintype "passive"))
    )
    (net (code "30") (name "Net-(IC1-1Z)") (class "Default")
      (node (ref "IC1") (pin "13") (pinfunction "1Z_13") (pintype "output"))
      (node (ref "N0183-TX") (pin "3") (pinfunction "3_3") (pintype "passive"))
    )
    (net (code "31") (name "Net-(IC1-2A)") (class "Default")
      (node (ref "IC1") (pin "6") (pinfunction "2A_6") (pintype "input"))
      (node (ref "N0183-RX") (pin "2") (pinfunction "2_2") (pintype "passive"))
    )
    (net (code "32") (name "Net-(IC1-2B)") (class "Default")
      (node (ref "IC1") (pin "7") (pinfunction "2B_7") (pintype "input"))
      (node (ref "N0183-RX") (pin "1") (pinfunction "1_1") (pintype "passive"))
    )
    (net (code "33") (name "Net-(IC1-2D)") (class "Default")
      (node (ref "IC1") (pin "9") (pinfunction "2D_9") (pintype "input"))
      (node (ref "OK4") (pin "4") (pinfunction "OUT_4") (pintype "output"))
      (node (ref "R17") (pin "1") (pinfunction "1_1") (pintype "passive"))
    )
    (net (code "34") (name "Net-(IC1-2R)") (class "Default")
      (node (ref "IC1") (pin "5") (pinfunction "2R_5") (pintype "output"))
      (node (ref "OK2") (pin "2") (pinfunction "C_2") (pintype "passive"))
    )
    (net (code "35") (name "Net-(IC1-2Y)") (class "Default")
      (node (ref "IC1") (pin "10") (pinfunction "2Y_10") (pintype "output"))
      (node (ref "N0183-TX") (pin "2") (pinfunction "2_2") (pintype "passive"))
    )
    (net (code "36") (name "Net-(IC1-2Z)") (class "Default")
      (node (ref "IC1") (pin "11") (pinfunction "2Z_11") (pintype "output"))
      (node (ref "N0183-TX") (pin "1") (pinfunction "1_1") (pintype "passive"))
    )
    (net (code "37") (name "Net-(JP2-CAN-H)") (class "Default")
      (node (ref "JP2") (pin "4") (pinfunction "CAN-H_4") (pintype "bidirectional"))
      (node (ref "NMEA2000") (pin "2") (pinfunction "2_2") (pintype "passive"))
      (node (ref "R1") (pin "2") (pinfunction "2_2") (pintype "passive"))
      (node (ref "U2") (pin "7") (pinfunction "CANH_7") (pintype "bidirectional"))
    )
    (net (code "38") (name "Net-(JP2-CAN-L)") (class "Default")
      (node (ref "JP2") (pin "5") (pinfunction "CAN-L_5") (pintype "bidirectional"))
      (node (ref "NMEA2000") (pin "3") (pinfunction "3_3") (pintype "passive"))
      (node (ref "SJ1") (pin "1") (pinfunction "1_1") (pintype "passive"))
      (node (ref "U2") (pin "6") (pinfunction "CANL_6") (pintype "bidirectional"))
    )
    (net (code "39") (name "Net-(LED1-PadA)") (class "Default")
      (node (ref "LED1") (pin "A") (pinfunction "A_A") (pintype "passive"))
      (node (ref "R23") (pin "2") (pinfunction "2_2") (pintype "passive"))
    )
    (net (code "40") (name "Net-(LED2-PadA)") (class "Default")
      (node (ref "LED2") (pin "A") (pinfunction "A_A") (pintype "passive"))
      (node (ref "R24") (pin "2") (pinfunction "2_2") (pintype "passive"))
    )
    (net (code "41") (name "Net-(LED3-PadA)") (class "Default")
      (node (ref "LED3") (pin "A") (pinfunction "A_A") (pintype "passive"))
      (node (ref "R25") (pin "2") (pinfunction "2_2") (pintype "passive"))
    )
    (net (code "42") (name "Net-(OK1-A)") (class "Default")
      (node (ref "OK1") (pin "1") (pinfunction "A_1") (pintype "passive"))
      (node (ref "R4") (pin "1") (pinfunction "1_1") (pintype "passive"))
    )
    (net (code "43") (name "Net-(OK2-A)") (class "Default")
      (node (ref "OK2") (pin "1") (pinfunction "A_1") (pintype "passive"))
      (node (ref "R3") (pin "1") (pinfunction "1_1") (pintype "passive"))
    )
    (net (code "44") (name "Net-(OK3-A)") (class "Default")
      (node (ref "OK3") (pin "1") (pinfunction "A_1") (pintype "passive"))
      (node (ref "R15") (pin "1") (pinfunction "1_1") (pintype "passive"))
    )
    (net (code "45") (name "Net-(OK4-A)") (class "Default")
      (node (ref "OK4") (pin "1") (pinfunction "A_1") (pintype "passive"))
      (node (ref "R16") (pin "1") (pinfunction "1_1") (pintype "passive"))
    )
    (net (code "46") (name "Net-(PROG-Pad1)") (class "Default")
      (node (ref "PROG") (pin "1") (pinfunction "1_1") (pintype "passive"))
      (node (ref "R31") (pin "1") (pinfunction "1_1") (pintype "passive"))
    )
    (net (code "47") (name "Net-(R1-Pad1)") (class "Default")
      (node (ref "R1") (pin "1") (pinfunction "1_1") (pintype "passive"))
      (node (ref "SJ1") (pin "2") (pinfunction "2_2") (pintype "passive"))
    )
    (net (code "48") (name "Net-(R20-Pad1)") (class "Default")
      (node (ref "R20") (pin "1") (pinfunction "1_1") (pintype "passive"))
      (node (ref "T1") (pin "B") (pinfunction "B_B") (pintype "passive"))
      (node (ref "Z2") (pin "K") (pinfunction "K_K") (pintype "bidirectional"))
    )
    (net (code "49") (name "Net-(R21-Pad1)") (class "Default")
      (node (ref "R21") (pin "1") (pinfunction "1_1") (pintype "passive"))
      (node (ref "R22") (pin "2") (pinfunction "2_2") (pintype "passive"))
      (node (ref "SJ3") (pin "2") (pinfunction "2_2") (pintype "passive"))
    )
    (net (code "50") (name "Net-(T2-B)") (class "Default")
      (node (ref "PROG") (pin "2") (pinfunction "2_2") (pintype "passive"))
      (node (ref "R35") (pin "2") (pinfunction "2_2") (pintype "passive"))
      (node (ref "T2") (pin "1") (pinfunction "B_1") (pintype "passive"))
      (node (ref "T3") (pin "1") (pinfunction "B_1") (pintype "passive"))
      (node (ref "T4") (pin "1") (pinfunction "B_1") (pintype "passive"))
    )
    (net (code "51") (name "Net-(U1-EN)") (class "Default")
      (node (ref "C7") (pin "1") (pinfunction "1_1") (pintype "passive"))
      (node (ref "R2") (pin "1") (pinfunction "1_1") (pintype "passive"))
      (node (ref "RESET") (pin "1") (pinfunction "1_1") (pintype "passive"))
      (node (ref "U1") (pin "3") (pinfunction "EN_3") (pintype "bidirectional"))
    )
    (net (code "52") (name "Net-(U1-GPIO16{slash}CAN-TX)") (class "Default")
      (node (ref "CAN") (pin "2") (pinfunction "2_2") (pintype "passive"))
      (node (ref "U1") (pin "27") (pinfunction "GPIO16/CAN-TX_27") (pintype "bidirectional"))
      (node (ref "U2") (pin "1") (pinfunction "TXD_1") (pintype "bidirectional"))
    )
    (net (code "53") (name "Net-(U1-GPIO17{slash}CAN-RX)") (class "Default")
      (node (ref "CAN") (pin "1") (pinfunction "1_1") (pintype "passive"))
      (node (ref "U1") (pin "28") (pinfunction "GPIO17/CAN-RX_28") (pintype "bidirectional"))
      (node (ref "U2") (pin "4") (pinfunction "RXD_4") (pintype "bidirectional"))
    )
    (net (code "54") (name "Net-(U1-GPIO21{slash}SDA)") (class "Default")
      (node (ref "I2C") (pin "1") (pinfunction "1_1") (pintype "passive"))
      (node (ref "R7") (pin "1") (pinfunction "1_1") (pintype "passive"))
      (node (ref "U1") (pin "33") (pinfunction "GPIO21/SDA_33") (pintype "bidirectional"))
      (node (ref "U3") (pin "14") (pinfunction "SDA_14") (pintype "bidirectional"))
    )
    (net (code "55") (name "Net-(U1-GPIO22{slash}SCL)") (class "Default")
      (node (ref "I2C") (pin "2") (pinfunction "2_2") (pintype "passive"))
      (node (ref "R36") (pin "1") (pinfunction "1_1") (pintype "passive"))
      (node (ref "U1") (pin "36") (pinfunction "GPIO22/SCL_36") (pintype "bidirectional"))
      (node (ref "U3") (pin "13") (pinfunction "SCL_13") (pintype "bidirectional"))
    )
    (net (code "56") (name "Net-(U1-GPIO25)") (class "Default")
      (node (ref "LED1") (pin "C") (pinfunction "C_C") (pintype "passive"))
      (node (ref "U1") (pin "10") (pinfunction "GPIO25_10") (pintype "bidirectional"))
    )
    (net (code "57") (name "Net-(U1-GPIO26)") (class "Default")
      (node (ref "LED2") (pin "C") (pinfunction "C_C") (pintype "passive"))
      (node (ref "U1") (pin "11") (pinfunction "GPIO26_11") (pintype "bidirectional"))
    )
    (net (code "58") (name "Net-(U1-GPIO27)") (class "Default")
      (node (ref "LED3") (pin "C") (pinfunction "C_C") (pintype "passive"))
      (node (ref "U1") (pin "12") (pinfunction "GPIO27_12") (pintype "bidirectional"))
    )
    (net (code "59") (name "Net-(U7-FB)") (class "Default")
      (node (ref "C4") (pin "1") (pinfunction "1_1") (pintype "passive"))
      (node (ref "R30") (pin "1") (pinfunction "1_1") (pintype "passive"))
      (node (ref "R32") (pin "2") (pinfunction "2_2") (pintype "passive"))
      (node (ref "U7") (pin "3") (pinfunction "FB_3") (pintype "bidirectional"))
    )
    (net (code "60") (name "OP_CUR_3V3_H") (class "Default")
      (node (ref "C6") (pin "1") (pinfunction "1_1") (pintype "passive"))
      (node (ref "POWER") (pin "11") (pinfunction "11_11") (pintype "passive"))
      (node (ref "R28") (pin "2") (pinfunction "2_2") (pintype "passive"))
      (node (ref "U4") (pin "2") (pinfunction "VOUT_2") (pintype "output"))
    )
    (net (code "61") (name "OP_CUR_5V_H") (class "Default")
      (node (ref "C19") (pin "2") (pinfunction "2_2") (pintype "passive"))
      (node (ref "C4") (pin "2") (pinfunction "2_2") (pintype "passive"))
      (node (ref "L1") (pin "P$2") (pinfunction "2_P$2") (pintype "passive"))
      (node (ref "POWER") (pin "9") (pinfunction "9_9") (pintype "passive"))
      (node (ref "R30") (pin "2") (pinfunction "2_2") (pintype "passive"))
      (node (ref "R33") (pin "2") (pinfunction "2_2") (pintype "passive"))
    )
    (net (code "62") (name "RX1") (class "Default")
      (node (ref "OK1") (pin "4") (pinfunction "OUT_4") (pintype "output"))
      (node (ref "R5") (pin "1") (pinfunction "1_1") (pintype "passive"))
      (node (ref "U1") (pin "6") (pinfunction "GPIO34_6") (pintype "bidirectional"))
    )
    (net (code "63") (name "RX2") (class "Default")
      (node (ref "OK2") (pin "4") (pinfunction "OUT_4") (pintype "output"))
      (node (ref "R6") (pin "1") (pinfunction "1_1") (pintype "passive"))
      (node (ref "U1") (pin "7") (pinfunction "GPIO35_7") (pintype "bidirectional"))
    )
    (net (code "64") (name "RXDATA") (class "Default")
      (node (ref "FTDI") (pin "5") (pinfunction "5_5") (pintype "passive"))
      (node (ref "U1") (pin "35") (pinfunction "GPIO1/TX0_35") (pintype "bidirectional"))
    )
    (net (code "65") (name "SCAP") (class "Default")
      (node (ref "C20") (pin "+") (pinfunction "+_+") (pintype "passive"))
      (node (ref "D4") (pin "A") (pinfunction "A_A") (pintype "bidirectional"))
      (node (ref "JP3") (pin "1") (pinfunction "1_1") (pintype "passive"))
      (node (ref "R19") (pin "1") (pinfunction "1_1") (pintype "passive"))
    )
    (net (code "66") (name "SCAPDRV") (class "Default")
      (node (ref "JP1") (pin "1") (pinfunction "1_1") (pintype "passive"))
      (node (ref "R19") (pin "2") (pinfunction "2_2") (pintype "passive"))
      (node (ref "T1") (pin "E") (pinfunction "E_E") (pintype "passive"))
    )
    (net (code "67") (name "TX1") (class "Default")
      (node (ref "OK3") (pin "2") (pinfunction "C_2") (pintype "passive"))
      (node (ref "U1") (pin "30") (pinfunction "GPIO18/V-CLK_30") (pintype "bidirectional"))
    )
    (net (code "68") (name "TX2") (class "Default")
      (node (ref "OK4") (pin "2") (pinfunction "C_2") (pintype "passive"))
      (node (ref "U1") (pin "31") (pinfunction "GPIO19/V-MISO_31") (pintype "bidirectional"))
    )
    (net (code "69") (name "TXDATA") (class "Default")
      (node (ref "FTDI") (pin "4") (pinfunction "4_4") (pintype "passive"))
      (node (ref "U1") (pin "34") (pinfunction "GPIO3/RX0_34") (pintype "bidirectional"))
    )
    (net (code "70") (name "VSENSE") (class "Default")
      (node (ref "POWER") (pin "3") (pinfunction "3_3") (pintype "passive"))
      (node (ref "R27") (pin "1") (pinfunction "1_1") (pintype "passive"))
      (node (ref "SJ2") (pin "1") (pinfunction "1_1") (pintype "passive"))
      (node (ref "SJ2") (pin "2") (pinfunction "2_2") (pintype "passive"))
      (node (ref "SJ3") (pin "1") (pinfunction "1_1") (pintype "passive"))
      (node (ref "U1") (pin "4") (pinfunction "GPI36/S-VP_4") (pintype "bidirectional"))
      (node (ref "Z1") (pin "2") (pinfunction "K_2") (pintype "bidirectional"))
    )
    (net (code "71") (name "unconnected-(FTDI-Pad2)") (class "Default")
      (node (ref "FTDI") (pin "2") (pinfunction "2_2") (pintype "passive"))
    )
    (net (code "72") (name "unconnected-(FTDI-Pad6)") (class "Default")
      (node (ref "FTDI") (pin "6") (pinfunction "6_6") (pintype "passive"))
    )
    (net (code "73") (name "unconnected-(H1-PadCD)") (class "Default")
      (node (ref "H1") (pin "CD") (pinfunction "CD_CD") (pintype "bidirectional"))
    )
    (net (code "74") (name "unconnected-(JP2-SHIELD-Pad1)") (class "Default")
      (node (ref "JP2") (pin "1") (pinfunction "SHIELD_1") (pintype "bidirectional"))
    )
    (net (code "75") (name "unconnected-(U1-GPIO5{slash}V-CS-Pad29)") (class "Default")
      (node (ref "U1") (pin "29") (pinfunction "GPIO5/V-CS_29") (pintype "bidirectional"))
    )
    (net (code "76") (name "unconnected-(U1-GPIO23{slash}V-MOSI-Pad37)") (class "Default")
      (node (ref "U1") (pin "37") (pinfunction "GPIO23/V-MOSI_37") (pintype "bidirectional"))
    )
    (net (code "77") (name "unconnected-(U1-GPIO32-Pad8)") (class "Default")
      (node (ref "U1") (pin "8") (pinfunction "GPIO32_8") (pintype "bidirectional"))
    )
    (net (code "78") (name "unconnected-(U1-GPIO33-Pad9)") (class "Default")
      (node (ref "U1") (pin "9") (pinfunction "GPIO33_9") (pintype "bidirectional"))
    )
    (net (code "79") (name "unconnected-(U3-INT2-Pad9)") (class "Default")
      (node (ref "U3") (pin "9") (pinfunction "INT2_9") (pintype "bidirectional"))
    )
  )
)
